# SWD.net
KiCad netlist of a schematic drawn in EAGLE
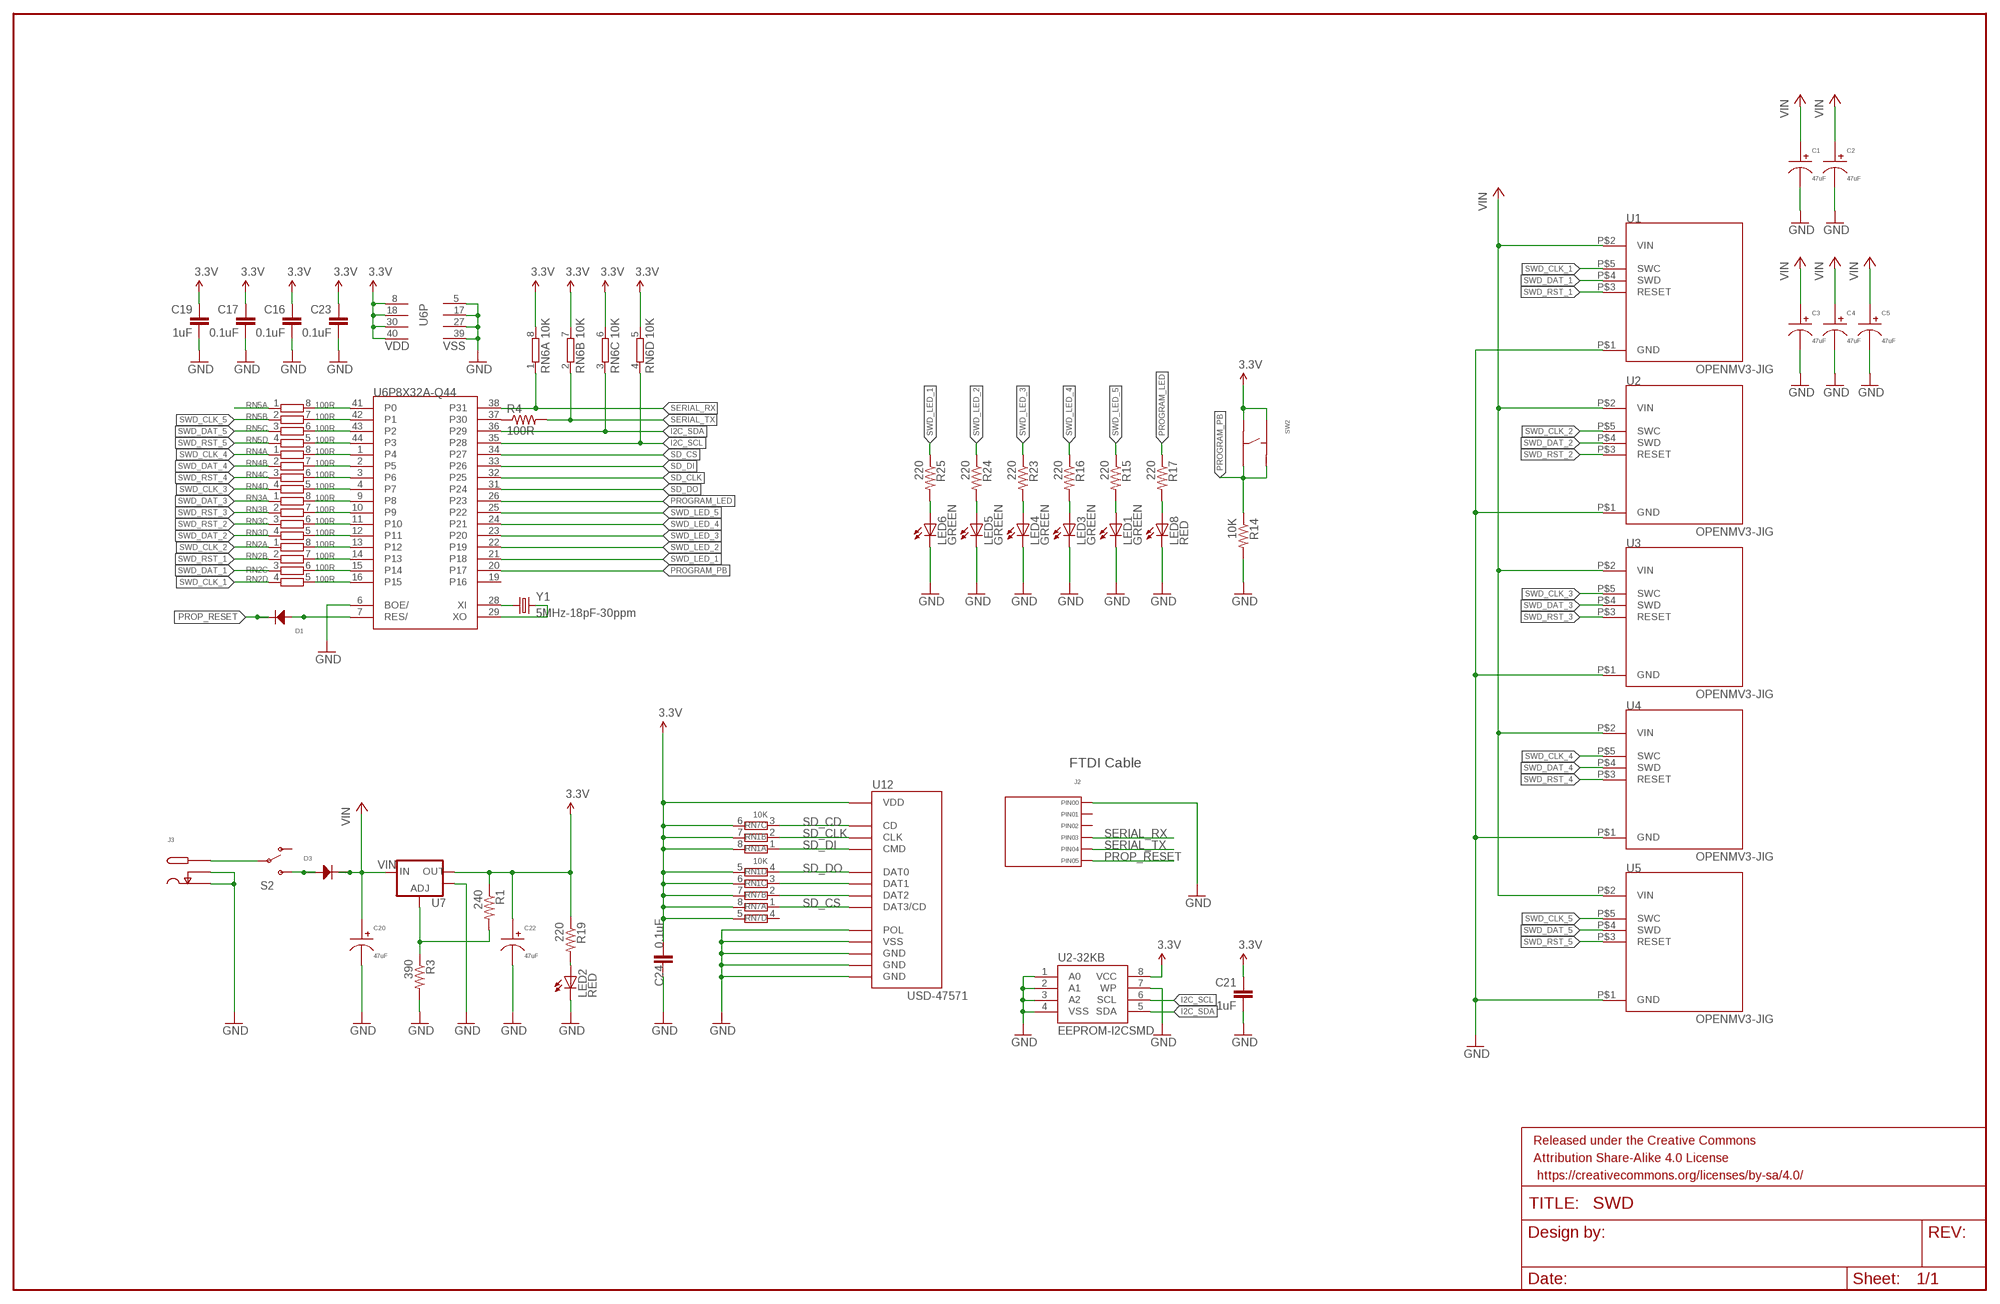
[diagram p0: schematic, sheet 1]

(export (version "E")
  (design (tool "Eeschema 10.0.6"))
  (components
    (comp (ref "C1")
      (value "47uF")
      (footprint "eagle-import:CP6.3MM")
      (fields (field (name "MFG#") "N/A") (field (name "TOLERANCE") "N/A") (field (name "VOTLAGE") "N/A"))
      (libsource (lib "eagle-import") (part "CAPACITOR_P_6.3MM"))
    )
    (comp (ref "C2")
      (value "47uF")
      (footprint "eagle-import:CP6.3MM")
      (fields (field (name "MFG#") "N/A") (field (name "TOLERANCE") "N/A") (field (name "VOTLAGE") "N/A"))
      (libsource (lib "eagle-import") (part "CAPACITOR_P_6.3MM"))
    )
    (comp (ref "C3")
      (value "47uF")
      (footprint "eagle-import:CP6.3MM")
      (fields (field (name "MFG#") "N/A") (field (name "TOLERANCE") "N/A") (field (name "VOTLAGE") "N/A"))
      (libsource (lib "eagle-import") (part "CAPACITOR_P_6.3MM"))
    )
    (comp (ref "C4")
      (value "47uF")
      (footprint "eagle-import:CP6.3MM")
      (fields (field (name "MFG#") "N/A") (field (name "TOLERANCE") "N/A") (field (name "VOTLAGE") "N/A"))
      (libsource (lib "eagle-import") (part "CAPACITOR_P_6.3MM"))
    )
    (comp (ref "C5")
      (value "47uF")
      (footprint "eagle-import:CP6.3MM")
      (fields (field (name "MFG#") "N/A") (field (name "TOLERANCE") "N/A") (field (name "VOTLAGE") "N/A"))
      (libsource (lib "eagle-import") (part "CAPACITOR_P_6.3MM"))
    )
    (comp (ref "C16")
      (value "0.1uF")
      (footprint "eagle-import:0603-CAP")
      (libsource (lib "eagle-import") (part "CAP0603-CAP"))
    )
    (comp (ref "C17")
      (value "0.1uF")
      (footprint "eagle-import:0603-CAP")
      (libsource (lib "eagle-import") (part "CAP0603-CAP"))
    )
    (comp (ref "C19")
      (value "1uF")
      (footprint "eagle-import:0603-CAP")
      (libsource (lib "eagle-import") (part "CAP0603-CAP"))
    )
    (comp (ref "C20")
      (value "47uF")
      (footprint "eagle-import:CP6.3MM")
      (libsource (lib "eagle-import") (part "CAPACITOR_P_6.3MM"))
    )
    (comp (ref "C21")
      (value "1uF")
      (footprint "eagle-import:0603-CAP")
      (libsource (lib "eagle-import") (part "CAP0603-CAP"))
    )
    (comp (ref "C22")
      (value "47uF")
      (footprint "eagle-import:CP6.3MM")
      (libsource (lib "eagle-import") (part "CAPACITOR_P_6.3MM"))
    )
    (comp (ref "C23")
      (value "0.1uF")
      (footprint "eagle-import:0603-CAP")
      (libsource (lib "eagle-import") (part "CAP0603-CAP"))
    )
    (comp (ref "C24")
      (value "0.1uF")
      (footprint "eagle-import:0603-CAP")
      (libsource (lib "eagle-import") (part "CAP0603-CAP"))
    )
    (comp (ref "D1")
      (value "DIODE_SOD-123")
      (footprint "eagle-import:SOD-123")
      (libsource (lib "eagle-import") (part "DIODE_SOD-123"))
    )
    (comp (ref "D3")
      (value "DIODE_SMA")
      (footprint "eagle-import:SMA")
      (libsource (lib "eagle-import") (part "DIODE_SMA"))
    )
    (comp (ref "FRAME1")
      (value "FRAME-LEDGER")
      (footprint "eagle-import:CREATIVE_COMMONS")
      (libsource (lib "eagle-import") (part "FRAME-LEDGER"))
    )
    (comp (ref "J2")
      (value "HEADER_01X06_PTH_2.54MM")
      (footprint "eagle-import:PTH_2.54MM_01X06")
      (libsource (lib "eagle-import") (part "HEADER_01X06_PTH_2.54MM"))
    )
    (comp (ref "J3")
      (value "DC_PWR_JACK_2.5MM_RIGHT")
      (footprint "eagle-import:DC_PWR_JACK")
      (libsource (lib "eagle-import") (part "DC_PWR_JACK_2.5MM_RIGHT"))
    )
    (comp (ref "LED1")
      (value "GREEN")
      (footprint "eagle-import:LED-0603")
      (libsource (lib "eagle-import") (part "LED0603"))
    )
    (comp (ref "LED2")
      (value "RED")
      (footprint "eagle-import:LED-0603")
      (libsource (lib "eagle-import") (part "LED0603"))
    )
    (comp (ref "LED3")
      (value "GREEN")
      (footprint "eagle-import:LED-0603")
      (libsource (lib "eagle-import") (part "LED0603"))
    )
    (comp (ref "LED4")
      (value "GREEN")
      (footprint "eagle-import:LED-0603")
      (libsource (lib "eagle-import") (part "LED0603"))
    )
    (comp (ref "LED5")
      (value "GREEN")
      (footprint "eagle-import:LED-0603")
      (libsource (lib "eagle-import") (part "LED0603"))
    )
    (comp (ref "LED6")
      (value "GREEN")
      (footprint "eagle-import:LED-0603")
      (libsource (lib "eagle-import") (part "LED0603"))
    )
    (comp (ref "LED8")
      (value "RED")
      (footprint "eagle-import:LED-0603")
      (libsource (lib "eagle-import") (part "LED0603"))
    )
    (comp (ref "R1")
      (value "240")
      (footprint "eagle-import:0603-RES")
      (libsource (lib "eagle-import") (part "RESISTOR0603-RES"))
    )
    (comp (ref "R3")
      (value "390")
      (footprint "eagle-import:0603-RES")
      (libsource (lib "eagle-import") (part "RESISTOR0603-RES"))
    )
    (comp (ref "R4")
      (value "100R")
      (footprint "eagle-import:0603-RES")
      (libsource (lib "eagle-import") (part "RESISTOR0603-RES"))
    )
    (comp (ref "R14")
      (value "10K")
      (footprint "eagle-import:0603-RES")
      (libsource (lib "eagle-import") (part "RESISTOR0603-RES"))
    )
    (comp (ref "R15")
      (value "220")
      (footprint "eagle-import:0603-RES")
      (libsource (lib "eagle-import") (part "RESISTOR0603-RES"))
    )
    (comp (ref "R16")
      (value "220")
      (footprint "eagle-import:0603-RES")
      (libsource (lib "eagle-import") (part "RESISTOR0603-RES"))
    )
    (comp (ref "R17")
      (value "220")
      (footprint "eagle-import:0603-RES")
      (libsource (lib "eagle-import") (part "RESISTOR0603-RES"))
    )
    (comp (ref "R19")
      (value "220")
      (footprint "eagle-import:0603-RES")
      (libsource (lib "eagle-import") (part "RESISTOR0603-RES"))
    )
    (comp (ref "R23")
      (value "220")
      (footprint "eagle-import:0603-RES")
      (libsource (lib "eagle-import") (part "RESISTOR0603-RES"))
    )
    (comp (ref "R24")
      (value "220")
      (footprint "eagle-import:0603-RES")
      (libsource (lib "eagle-import") (part "RESISTOR0603-RES"))
    )
    (comp (ref "R25")
      (value "220")
      (footprint "eagle-import:0603-RES")
      (libsource (lib "eagle-import") (part "RESISTOR0603-RES"))
    )
    (comp (ref "RN1")
      (value "10K")
      (footprint "eagle-import:EXBV8V")
      (fields (field (name "OC_FARNELL") "unknown") (field (name "OC_NEWARK") "unknown"))
      (libsource (lib "eagle-import") (part "4R-NEXBV8V"))
    )
    (comp (ref "RN2")
      (value "100R")
      (footprint "eagle-import:EXBV8V")
      (fields (field (name "OC_FARNELL") "unknown") (field (name "OC_NEWARK") "unknown"))
      (libsource (lib "eagle-import") (part "4R-NEXBV8V"))
    )
    (comp (ref "RN3")
      (value "100R")
      (footprint "eagle-import:EXBV8V")
      (fields (field (name "OC_FARNELL") "unknown") (field (name "OC_NEWARK") "unknown"))
      (libsource (lib "eagle-import") (part "4R-NEXBV8V"))
    )
    (comp (ref "RN4")
      (value "100R")
      (footprint "eagle-import:EXBV8V")
      (fields (field (name "OC_FARNELL") "unknown") (field (name "OC_NEWARK") "unknown"))
      (libsource (lib "eagle-import") (part "4R-NEXBV8V"))
    )
    (comp (ref "RN5")
      (value "100R")
      (footprint "eagle-import:EXBV8V")
      (fields (field (name "OC_FARNELL") "unknown") (field (name "OC_NEWARK") "unknown"))
      (libsource (lib "eagle-import") (part "4R-NEXBV8V"))
    )
    (comp (ref "RN6")
      (value "10K")
      (footprint "eagle-import:EXBV8V")
      (fields (field (name "OC_FARNELL") "unknown") (field (name "OC_NEWARK") "unknown"))
      (libsource (lib "eagle-import") (part "4R-NEXBV8V"))
    )
    (comp (ref "RN7")
      (value "10K")
      (footprint "eagle-import:EXBV8V")
      (fields (field (name "OC_FARNELL") "unknown") (field (name "OC_NEWARK") "unknown"))
      (libsource (lib "eagle-import") (part "4R-NEXBV8V"))
    )
    (comp (ref "S2")
      (value "SWITCH-SPSTPTH")
      (footprint "eagle-import:SWITCH-SPDT")
      (libsource (lib "eagle-import") (part "SWITCH-SPSTPTH"))
    )
    (comp (ref "SW2")
      (value "TACT_6MM")
      (footprint "eagle-import:TACT6MM")
      (libsource (lib "eagle-import") (part "TACT_6MM"))
    )
    (comp (ref "U1")
      (value "OPENMV3-JIG")
      (footprint "eagle-import:OPENMV3-JIG")
      (libsource (lib "eagle-import") (part "OPENMV3-JIG"))
    )
    (comp (ref "U2")
      (value "OPENMV3-JIG")
      (footprint "eagle-import:OPENMV3-JIG")
      (libsource (lib "eagle-import") (part "OPENMV3-JIG"))
    )
    (comp (ref "U2-32KB")
      (value "EEPROM-I2CSMD")
      (footprint "eagle-import:SO08")
      (libsource (lib "eagle-import") (part "EEPROM-I2CSMD"))
    )
    (comp (ref "U3")
      (value "OPENMV3-JIG")
      (footprint "eagle-import:OPENMV3-JIG")
      (libsource (lib "eagle-import") (part "OPENMV3-JIG"))
    )
    (comp (ref "U4")
      (value "OPENMV3-JIG")
      (footprint "eagle-import:OPENMV3-JIG")
      (libsource (lib "eagle-import") (part "OPENMV3-JIG"))
    )
    (comp (ref "U5")
      (value "OPENMV3-JIG")
      (footprint "eagle-import:OPENMV3-JIG")
      (libsource (lib "eagle-import") (part "OPENMV3-JIG"))
    )
    (comp (ref "U6")
      (value "P8X32A-Q44")
      (footprint "eagle-import:P8X32A-Q44")
      (libsource (lib "eagle-import") (part "P8X32A-Q44"))
    )
    (comp (ref "U7")
      (value "V_REG_LM1117SOT223")
      (footprint "eagle-import:SOT223")
      (libsource (lib "eagle-import") (part "V_REG_LM1117SOT223"))
    )
    (comp (ref "U12")
      (value "USD-47571")
      (footprint "eagle-import:USD-47571")
      (libsource (lib "eagle-import") (part "USD-47571"))
    )
    (comp (ref "Y1")
      (value "5MHz-18pF-30ppm")
      (footprint "eagle-import:HC49UP")
      (libsource (lib "eagle-import") (part "CRYSTALSMD"))
    )
  )
  (nets
    (net (code "1") (name "/SD_CD") (class "Default")
      (node (ref "RN7") (pin "3") (pinfunction "1_3") (pintype "passive"))
      (node (ref "U12") (pin "G$5") (pinfunction "CD_G$5") (pintype "power_in"))
    )
    (net (code "2") (name "3.3V") (class "Default")
      (node (ref "C16") (pin "1") (pinfunction "1_1") (pintype "passive"))
      (node (ref "C17") (pin "1") (pinfunction "1_1") (pintype "passive"))
      (node (ref "C19") (pin "1") (pinfunction "1_1") (pintype "passive"))
      (node (ref "C21") (pin "1") (pinfunction "1_1") (pintype "passive"))
      (node (ref "C22") (pin "P$1") (pinfunction "P$1_P$1") (pintype "passive"))
      (node (ref "C23") (pin "1") (pinfunction "1_1") (pintype "passive"))
      (node (ref "C24") (pin "1") (pinfunction "1_1") (pintype "passive"))
      (node (ref "R1") (pin "1") (pinfunction "1_1") (pintype "passive"))
      (node (ref "R19") (pin "1") (pinfunction "1_1") (pintype "passive"))
      (node (ref "RN1") (pin "5") (pinfunction "2_5") (pintype "passive"))
      (node (ref "RN1") (pin "6") (pinfunction "2_6") (pintype "passive"))
      (node (ref "RN1") (pin "7") (pinfunction "2_7") (pintype "passive"))
      (node (ref "RN1") (pin "8") (pinfunction "2_8") (pintype "passive"))
      (node (ref "RN6") (pin "5") (pinfunction "2_5") (pintype "passive"))
      (node (ref "RN6") (pin "6") (pinfunction "2_6") (pintype "passive"))
      (node (ref "RN6") (pin "7") (pinfunction "2_7") (pintype "passive"))
      (node (ref "RN6") (pin "8") (pinfunction "2_8") (pintype "passive"))
      (node (ref "RN7") (pin "5") (pinfunction "2_5") (pintype "passive"))
      (node (ref "RN7") (pin "6") (pinfunction "2_6") (pintype "passive"))
      (node (ref "RN7") (pin "7") (pinfunction "2_7") (pintype "passive"))
      (node (ref "RN7") (pin "8") (pinfunction "2_8") (pintype "passive"))
      (node (ref "SW2") (pin "P$1") (pinfunction "P$1_P$1") (pintype "bidirectional"))
      (node (ref "SW2") (pin "P$3") (pinfunction "P$3_P$3") (pintype "bidirectional"))
      (node (ref "U12") (pin "P$4") (pinfunction "VDD_P$4") (pintype "power_in"))
      (node (ref "U2-32KB") (pin "8") (pinfunction "VCC_8") (pintype "power_in"))
      (node (ref "U6") (pin "18") (pinfunction "VDD_18") (pintype "power_in"))
      (node (ref "U6") (pin "30") (pinfunction "VDD_30") (pintype "power_in"))
      (node (ref "U6") (pin "40") (pinfunction "VDD_40") (pintype "power_in"))
      (node (ref "U6") (pin "8") (pinfunction "VDD_8") (pintype "power_in"))
      (node (ref "U7") (pin "2") (pinfunction "OUT_2") (pintype "output"))
    )
    (net (code "3") (name "GND") (class "Default")
      (node (ref "C1") (pin "P$2") (pinfunction "P$2_P$2") (pintype "passive"))
      (node (ref "C16") (pin "2") (pinfunction "2_2") (pintype "passive"))
      (node (ref "C17") (pin "2") (pinfunction "2_2") (pintype "passive"))
      (node (ref "C19") (pin "2") (pinfunction "2_2") (pintype "passive"))
      (node (ref "C2") (pin "P$2") (pinfunction "P$2_P$2") (pintype "passive"))
      (node (ref "C20") (pin "P$2") (pinfunction "P$2_P$2") (pintype "passive"))
      (node (ref "C21") (pin "2") (pinfunction "2_2") (pintype "passive"))
      (node (ref "C22") (pin "P$2") (pinfunction "P$2_P$2") (pintype "passive"))
      (node (ref "C23") (pin "2") (pinfunction "2_2") (pintype "passive"))
      (node (ref "C24") (pin "2") (pinfunction "2_2") (pintype "passive"))
      (node (ref "C3") (pin "P$2") (pinfunction "P$2_P$2") (pintype "passive"))
      (node (ref "C4") (pin "P$2") (pinfunction "P$2_P$2") (pintype "passive"))
      (node (ref "C5") (pin "P$2") (pinfunction "P$2_P$2") (pintype "passive"))
      (node (ref "J2") (pin "P$1") (pinfunction "PIN0_P$1") (pintype "bidirectional"))
      (node (ref "J3") (pin "SLEEVE1") (pinfunction "SLEEVE_SLEEVE1") (pintype "power_in"))
      (node (ref "J3") (pin "SLEEVE2") (pinfunction "SLEEVE_SHUNT_SLEEVE2") (pintype "power_in"))
      (node (ref "LED1") (pin "C") (pinfunction "C_C") (pintype "passive"))
      (node (ref "LED2") (pin "C") (pinfunction "C_C") (pintype "passive"))
      (node (ref "LED3") (pin "C") (pinfunction "C_C") (pintype "passive"))
      (node (ref "LED4") (pin "C") (pinfunction "C_C") (pintype "passive"))
      (node (ref "LED5") (pin "C") (pinfunction "C_C") (pintype "passive"))
      (node (ref "LED6") (pin "C") (pinfunction "C_C") (pintype "passive"))
      (node (ref "LED8") (pin "C") (pinfunction "C_C") (pintype "passive"))
      (node (ref "R14") (pin "2") (pinfunction "2_2") (pintype "passive"))
      (node (ref "R3") (pin "2") (pinfunction "2_2") (pintype "passive"))
      (node (ref "U1") (pin "P$1") (pinfunction "GND_P$1") (pintype "power_in"))
      (node (ref "U12") (pin "G$1") (pinfunction "GND_G$1") (pintype "power_in"))
      (node (ref "U12") (pin "G$2") (pinfunction "GND_G$2") (pintype "power_in"))
      (node (ref "U12") (pin "G$3") (pinfunction "GND_G$3") (pintype "power_in"))
      (node (ref "U12") (pin "G$4") (pinfunction "POL_G$4") (pintype "power_in"))
      (node (ref "U12") (pin "P$6") (pinfunction "VSS_P$6") (pintype "power_in"))
      (node (ref "U2") (pin "P$1") (pinfunction "GND_P$1") (pintype "power_in"))
      (node (ref "U2-32KB") (pin "1") (pinfunction "A0_1") (pintype "bidirectional"))
      (node (ref "U2-32KB") (pin "2") (pinfunction "A1_2") (pintype "bidirectional"))
      (node (ref "U2-32KB") (pin "3") (pinfunction "A2_3") (pintype "bidirectional"))
      (node (ref "U2-32KB") (pin "4") (pinfunction "VSS_4") (pintype "power_in"))
      (node (ref "U2-32KB") (pin "7") (pinfunction "WP_7") (pintype "bidirectional"))
      (node (ref "U3") (pin "P$1") (pinfunction "GND_P$1") (pintype "power_in"))
      (node (ref "U4") (pin "P$1") (pinfunction "GND_P$1") (pintype "power_in"))
      (node (ref "U5") (pin "P$1") (pinfunction "GND_P$1") (pintype "power_in"))
      (node (ref "U6") (pin "17") (pinfunction "VSS_17") (pintype "power_in"))
      (node (ref "U6") (pin "27") (pinfunction "VSS_27") (pintype "power_in"))
      (node (ref "U6") (pin "39") (pinfunction "VSS_39") (pintype "power_in"))
      (node (ref "U6") (pin "5") (pinfunction "VSS_5") (pintype "power_in"))
      (node (ref "U6") (pin "6") (pinfunction "BOE/_6") (pintype "input"))
      (node (ref "U7") (pin "4") (pinfunction "OUT_4") (pintype "output"))
    )
    (net (code "4") (name "I2C_SCL") (class "Default")
      (node (ref "RN6") (pin "4") (pinfunction "1_4") (pintype "passive"))
      (node (ref "U2-32KB") (pin "6") (pinfunction "SCL_6") (pintype "bidirectional"))
      (node (ref "U6") (pin "35") (pinfunction "P28_35") (pintype "bidirectional"))
    )
    (net (code "5") (name "I2C_SDA") (class "Default")
      (node (ref "RN6") (pin "3") (pinfunction "1_3") (pintype "passive"))
      (node (ref "U2-32KB") (pin "5") (pinfunction "SDA_5") (pintype "bidirectional"))
      (node (ref "U6") (pin "36") (pinfunction "P29_36") (pintype "bidirectional"))
    )
    (net (code "6") (name "Net-(LED1-PadA)") (class "Default")
      (node (ref "LED1") (pin "A") (pinfunction "A_A") (pintype "passive"))
      (node (ref "R15") (pin "2") (pinfunction "2_2") (pintype "passive"))
    )
    (net (code "7") (name "Net-(LED2-PadA)") (class "Default")
      (node (ref "LED2") (pin "A") (pinfunction "A_A") (pintype "passive"))
      (node (ref "R19") (pin "2") (pinfunction "2_2") (pintype "passive"))
    )
    (net (code "8") (name "Net-(LED3-PadA)") (class "Default")
      (node (ref "LED3") (pin "A") (pinfunction "A_A") (pintype "passive"))
      (node (ref "R16") (pin "2") (pinfunction "2_2") (pintype "passive"))
    )
    (net (code "9") (name "Net-(LED4-PadA)") (class "Default")
      (node (ref "LED4") (pin "A") (pinfunction "A_A") (pintype "passive"))
      (node (ref "R23") (pin "2") (pinfunction "2_2") (pintype "passive"))
    )
    (net (code "10") (name "Net-(LED5-PadA)") (class "Default")
      (node (ref "LED5") (pin "A") (pinfunction "A_A") (pintype "passive"))
      (node (ref "R24") (pin "2") (pinfunction "2_2") (pintype "passive"))
    )
    (net (code "11") (name "Net-(LED6-PadA)") (class "Default")
      (node (ref "LED6") (pin "A") (pinfunction "A_A") (pintype "passive"))
      (node (ref "R25") (pin "2") (pinfunction "2_2") (pintype "passive"))
    )
    (net (code "12") (name "Net-(LED8-PadA)") (class "Default")
      (node (ref "LED8") (pin "A") (pinfunction "A_A") (pintype "passive"))
      (node (ref "R17") (pin "2") (pinfunction "2_2") (pintype "passive"))
    )
    (net (code "13") (name "Net-(RN1C-1)") (class "Default")
      (node (ref "RN1") (pin "3") (pinfunction "1_3") (pintype "passive"))
      (node (ref "U12") (pin "P$8") (pinfunction "DAT1_P$8") (pintype "bidirectional"))
    )
    (net (code "14") (name "Net-(RN2A-2)") (class "Default")
      (node (ref "RN2") (pin "8") (pinfunction "2_8") (pintype "passive"))
      (node (ref "U6") (pin "13") (pinfunction "P12_13") (pintype "bidirectional"))
    )
    (net (code "15") (name "Net-(RN2B-2)") (class "Default")
      (node (ref "RN2") (pin "7") (pinfunction "2_7") (pintype "passive"))
      (node (ref "U6") (pin "14") (pinfunction "P13_14") (pintype "bidirectional"))
    )
    (net (code "16") (name "Net-(RN2C-2)") (class "Default")
      (node (ref "RN2") (pin "6") (pinfunction "2_6") (pintype "passive"))
      (node (ref "U6") (pin "15") (pinfunction "P14_15") (pintype "bidirectional"))
    )
    (net (code "17") (name "Net-(RN2D-2)") (class "Default")
      (node (ref "RN2") (pin "5") (pinfunction "2_5") (pintype "passive"))
      (node (ref "U6") (pin "16") (pinfunction "P15_16") (pintype "bidirectional"))
    )
    (net (code "18") (name "Net-(RN3A-2)") (class "Default")
      (node (ref "RN3") (pin "8") (pinfunction "2_8") (pintype "passive"))
      (node (ref "U6") (pin "9") (pinfunction "P8_9") (pintype "bidirectional"))
    )
    (net (code "19") (name "Net-(RN3B-2)") (class "Default")
      (node (ref "RN3") (pin "7") (pinfunction "2_7") (pintype "passive"))
      (node (ref "U6") (pin "10") (pinfunction "P9_10") (pintype "bidirectional"))
    )
    (net (code "20") (name "Net-(RN3C-2)") (class "Default")
      (node (ref "RN3") (pin "6") (pinfunction "2_6") (pintype "passive"))
      (node (ref "U6") (pin "11") (pinfunction "P10_11") (pintype "bidirectional"))
    )
    (net (code "21") (name "Net-(RN3D-2)") (class "Default")
      (node (ref "RN3") (pin "5") (pinfunction "2_5") (pintype "passive"))
      (node (ref "U6") (pin "12") (pinfunction "P11_12") (pintype "bidirectional"))
    )
    (net (code "22") (name "Net-(RN4A-2)") (class "Default")
      (node (ref "RN4") (pin "8") (pinfunction "2_8") (pintype "passive"))
      (node (ref "U6") (pin "1") (pinfunction "P4_1") (pintype "bidirectional"))
    )
    (net (code "23") (name "Net-(RN4B-2)") (class "Default")
      (node (ref "RN4") (pin "7") (pinfunction "2_7") (pintype "passive"))
      (node (ref "U6") (pin "2") (pinfunction "P5_2") (pintype "bidirectional"))
    )
    (net (code "24") (name "Net-(RN4C-2)") (class "Default")
      (node (ref "RN4") (pin "6") (pinfunction "2_6") (pintype "passive"))
      (node (ref "U6") (pin "3") (pinfunction "P6_3") (pintype "bidirectional"))
    )
    (net (code "25") (name "Net-(RN4D-2)") (class "Default")
      (node (ref "RN4") (pin "5") (pinfunction "2_5") (pintype "passive"))
      (node (ref "U6") (pin "4") (pinfunction "P7_4") (pintype "bidirectional"))
    )
    (net (code "26") (name "Net-(RN5A-2)") (class "Default")
      (node (ref "RN5") (pin "8") (pinfunction "2_8") (pintype "passive"))
      (node (ref "U6") (pin "41") (pinfunction "P0_41") (pintype "bidirectional"))
    )
    (net (code "27") (name "Net-(RN5B-2)") (class "Default")
      (node (ref "RN5") (pin "7") (pinfunction "2_7") (pintype "passive"))
      (node (ref "U6") (pin "42") (pinfunction "P1_42") (pintype "bidirectional"))
    )
    (net (code "28") (name "Net-(RN5C-2)") (class "Default")
      (node (ref "RN5") (pin "6") (pinfunction "2_6") (pintype "passive"))
      (node (ref "U6") (pin "43") (pinfunction "P2_43") (pintype "bidirectional"))
    )
    (net (code "29") (name "Net-(RN5D-2)") (class "Default")
      (node (ref "RN5") (pin "5") (pinfunction "2_5") (pintype "passive"))
      (node (ref "U6") (pin "44") (pinfunction "P3_44") (pintype "bidirectional"))
    )
    (net (code "30") (name "Net-(RN7B-1)") (class "Default")
      (node (ref "RN7") (pin "2") (pinfunction "1_2") (pintype "passive"))
      (node (ref "U12") (pin "P$1") (pinfunction "DAT2_P$1") (pintype "bidirectional"))
    )
    (net (code "31") (name "Net-(S2-P)") (class "Default")
      (node (ref "J3") (pin "PIN") (pinfunction "PIN_PIN") (pintype "power_in"))
      (node (ref "S2") (pin "2") (pinfunction "P_2") (pintype "passive"))
    )
    (net (code "32") (name "Net-(S2-S)") (class "Default")
      (node (ref "D3") (pin "ANODE") (pinfunction "ANODE_ANODE") (pintype "bidirectional"))
      (node (ref "S2") (pin "3") (pinfunction "S_3") (pintype "passive"))
    )
    (net (code "33") (name "Net-(U6B-P30)") (class "Default")
      (node (ref "R4") (pin "1") (pinfunction "1_1") (pintype "passive"))
      (node (ref "U6") (pin "37") (pinfunction "P30_37") (pintype "bidirectional"))
    )
    (net (code "34") (name "Net-(U6B-RES{slash})") (class "Default")
      (node (ref "D1") (pin "ANODE") (pinfunction "ANODE_ANODE") (pintype "bidirectional"))
      (node (ref "U6") (pin "7") (pinfunction "RES/_7") (pintype "bidirectional"))
    )
    (net (code "35") (name "Net-(U6B-XI)") (class "Default")
      (node (ref "U6") (pin "28") (pinfunction "XI_28") (pintype "input"))
      (node (ref "Y1") (pin "1") (pinfunction "1_1") (pintype "passive"))
    )
    (net (code "36") (name "Net-(U6B-XO)") (class "Default")
      (node (ref "U6") (pin "29") (pinfunction "XO_29") (pintype "output"))
      (node (ref "Y1") (pin "2") (pinfunction "2_2") (pintype "passive"))
    )
    (net (code "37") (name "Net-(U7-ADJ)") (class "Default")
      (node (ref "R1") (pin "2") (pinfunction "2_2") (pintype "passive"))
      (node (ref "R3") (pin "1") (pinfunction "1_1") (pintype "passive"))
      (node (ref "U7") (pin "1") (pinfunction "ADJ_1") (pintype "input"))
    )
    (net (code "38") (name "PROGRAM_LED") (class "Default")
      (node (ref "R17") (pin "1") (pinfunction "1_1") (pintype "passive"))
      (node (ref "U6") (pin "26") (pinfunction "P23_26") (pintype "bidirectional"))
    )
    (net (code "39") (name "PROGRAM_PB") (class "Default")
      (node (ref "R14") (pin "1") (pinfunction "1_1") (pintype "passive"))
      (node (ref "SW2") (pin "P$2") (pinfunction "P$2_P$2") (pintype "bidirectional"))
      (node (ref "SW2") (pin "P$4") (pinfunction "P$4_P$4") (pintype "bidirectional"))
      (node (ref "U6") (pin "20") (pinfunction "P17_20") (pintype "bidirectional"))
    )
    (net (code "40") (name "PROP_RESET") (class "Default")
      (node (ref "D1") (pin "CATHODE") (pinfunction "CATHODE_CATHODE") (pintype "bidirectional"))
      (node (ref "J2") (pin "P$6") (pinfunction "PIN5_P$6") (pintype "bidirectional"))
    )
    (net (code "41") (name "SD_CLK") (class "Default")
      (node (ref "RN1") (pin "2") (pinfunction "1_2") (pintype "passive"))
      (node (ref "U12") (pin "P$5") (pinfunction "CLK_P$5") (pintype "bidirectional"))
      (node (ref "U6") (pin "32") (pinfunction "P25_32") (pintype "bidirectional"))
    )
    (net (code "42") (name "SD_CS") (class "Default")
      (node (ref "RN7") (pin "1") (pinfunction "1_1") (pintype "passive"))
      (node (ref "U12") (pin "P$2") (pinfunction "DAT3/CD_P$2") (pintype "bidirectional"))
      (node (ref "U6") (pin "34") (pinfunction "P27_34") (pintype "bidirectional"))
    )
    (net (code "43") (name "SD_DI") (class "Default")
      (node (ref "RN1") (pin "1") (pinfunction "1_1") (pintype "passive"))
      (node (ref "U12") (pin "P$3") (pinfunction "CMD_P$3") (pintype "bidirectional"))
      (node (ref "U6") (pin "33") (pinfunction "P26_33") (pintype "bidirectional"))
    )
    (net (code "44") (name "SD_DO") (class "Default")
      (node (ref "RN1") (pin "4") (pinfunction "1_4") (pintype "passive"))
      (node (ref "U12") (pin "P$7") (pinfunction "DAT0_P$7") (pintype "bidirectional"))
      (node (ref "U6") (pin "31") (pinfunction "P24_31") (pintype "bidirectional"))
    )
    (net (code "45") (name "SERIAL_RX") (class "Default")
      (node (ref "J2") (pin "P$4") (pinfunction "PIN3_P$4") (pintype "bidirectional"))
      (node (ref "RN6") (pin "1") (pinfunction "1_1") (pintype "passive"))
      (node (ref "U6") (pin "38") (pinfunction "P31_38") (pintype "bidirectional"))
    )
    (net (code "46") (name "SERIAL_TX") (class "Default")
      (node (ref "J2") (pin "P$5") (pinfunction "PIN4_P$5") (pintype "bidirectional"))
      (node (ref "R4") (pin "2") (pinfunction "2_2") (pintype "passive"))
      (node (ref "RN6") (pin "2") (pinfunction "1_2") (pintype "passive"))
    )
    (net (code "47") (name "SWD_CLK_1") (class "Default")
      (node (ref "RN2") (pin "4") (pinfunction "1_4") (pintype "passive"))
      (node (ref "U1") (pin "P$5") (pinfunction "SWC_P$5") (pintype "bidirectional"))
    )
    (net (code "48") (name "SWD_CLK_2") (class "Default")
      (node (ref "RN2") (pin "1") (pinfunction "1_1") (pintype "passive"))
      (node (ref "U2") (pin "P$5") (pinfunction "SWC_P$5") (pintype "bidirectional"))
    )
    (net (code "49") (name "SWD_CLK_3") (class "Default")
      (node (ref "RN4") (pin "4") (pinfunction "1_4") (pintype "passive"))
      (node (ref "U3") (pin "P$5") (pinfunction "SWC_P$5") (pintype "bidirectional"))
    )
    (net (code "50") (name "SWD_CLK_4") (class "Default")
      (node (ref "RN4") (pin "1") (pinfunction "1_1") (pintype "passive"))
      (node (ref "U4") (pin "P$5") (pinfunction "SWC_P$5") (pintype "bidirectional"))
    )
    (net (code "51") (name "SWD_CLK_5") (class "Default")
      (node (ref "RN5") (pin "2") (pinfunction "1_2") (pintype "passive"))
      (node (ref "U5") (pin "P$5") (pinfunction "SWC_P$5") (pintype "bidirectional"))
    )
    (net (code "52") (name "SWD_DAT_1") (class "Default")
      (node (ref "RN2") (pin "3") (pinfunction "1_3") (pintype "passive"))
      (node (ref "U1") (pin "P$4") (pinfunction "SWD_P$4") (pintype "bidirectional"))
    )
    (net (code "53") (name "SWD_DAT_2") (class "Default")
      (node (ref "RN3") (pin "4") (pinfunction "1_4") (pintype "passive"))
      (node (ref "U2") (pin "P$4") (pinfunction "SWD_P$4") (pintype "bidirectional"))
    )
    (net (code "54") (name "SWD_DAT_3") (class "Default")
      (node (ref "RN3") (pin "1") (pinfunction "1_1") (pintype "passive"))
      (node (ref "U3") (pin "P$4") (pinfunction "SWD_P$4") (pintype "bidirectional"))
    )
    (net (code "55") (name "SWD_DAT_4") (class "Default")
      (node (ref "RN4") (pin "2") (pinfunction "1_2") (pintype "passive"))
      (node (ref "U4") (pin "P$4") (pinfunction "SWD_P$4") (pintype "bidirectional"))
    )
    (net (code "56") (name "SWD_DAT_5") (class "Default")
      (node (ref "RN5") (pin "3") (pinfunction "1_3") (pintype "passive"))
      (node (ref "U5") (pin "P$4") (pinfunction "SWD_P$4") (pintype "bidirectional"))
    )
    (net (code "57") (name "SWD_LED_1") (class "Default")
      (node (ref "R25") (pin "1") (pinfunction "1_1") (pintype "passive"))
      (node (ref "U6") (pin "21") (pinfunction "P18_21") (pintype "bidirectional"))
    )
    (net (code "58") (name "SWD_LED_2") (class "Default")
      (node (ref "R24") (pin "1") (pinfunction "1_1") (pintype "passive"))
      (node (ref "U6") (pin "22") (pinfunction "P19_22") (pintype "bidirectional"))
    )
    (net (code "59") (name "SWD_LED_3") (class "Default")
      (node (ref "R23") (pin "1") (pinfunction "1_1") (pintype "passive"))
      (node (ref "U6") (pin "23") (pinfunction "P20_23") (pintype "bidirectional"))
    )
    (net (code "60") (name "SWD_LED_4") (class "Default")
      (node (ref "R16") (pin "1") (pinfunction "1_1") (pintype "passive"))
      (node (ref "U6") (pin "24") (pinfunction "P21_24") (pintype "bidirectional"))
    )
    (net (code "61") (name "SWD_LED_5") (class "Default")
      (node (ref "R15") (pin "1") (pinfunction "1_1") (pintype "passive"))
      (node (ref "U6") (pin "25") (pinfunction "P22_25") (pintype "bidirectional"))
    )
    (net (code "62") (name "SWD_RST_1") (class "Default")
      (node (ref "RN2") (pin "2") (pinfunction "1_2") (pintype "passive"))
      (node (ref "U1") (pin "P$3") (pinfunction "RESET_P$3") (pintype "bidirectional"))
    )
    (net (code "63") (name "SWD_RST_2") (class "Default")
      (node (ref "RN3") (pin "3") (pinfunction "1_3") (pintype "passive"))
      (node (ref "U2") (pin "P$3") (pinfunction "RESET_P$3") (pintype "bidirectional"))
    )
    (net (code "64") (name "SWD_RST_3") (class "Default")
      (node (ref "RN3") (pin "2") (pinfunction "1_2") (pintype "passive"))
      (node (ref "U3") (pin "P$3") (pinfunction "RESET_P$3") (pintype "bidirectional"))
    )
    (net (code "65") (name "SWD_RST_4") (class "Default")
      (node (ref "RN4") (pin "3") (pinfunction "1_3") (pintype "passive"))
      (node (ref "U4") (pin "P$3") (pinfunction "RESET_P$3") (pintype "bidirectional"))
    )
    (net (code "66") (name "SWD_RST_5") (class "Default")
      (node (ref "RN5") (pin "4") (pinfunction "1_4") (pintype "passive"))
      (node (ref "U5") (pin "P$3") (pinfunction "RESET_P$3") (pintype "bidirectional"))
    )
    (net (code "67") (name "VIN") (class "Default")
      (node (ref "C1") (pin "P$1") (pinfunction "P$1_P$1") (pintype "passive"))
      (node (ref "C2") (pin "P$1") (pinfunction "P$1_P$1") (pintype "passive"))
      (node (ref "C20") (pin "P$1") (pinfunction "P$1_P$1") (pintype "passive"))
      (node (ref "C3") (pin "P$1") (pinfunction "P$1_P$1") (pintype "passive"))
      (node (ref "C4") (pin "P$1") (pinfunction "P$1_P$1") (pintype "passive"))
      (node (ref "C5") (pin "P$1") (pinfunction "P$1_P$1") (pintype "passive"))
      (node (ref "D3") (pin "CATHODE") (pinfunction "CATHODE_CATHODE") (pintype "bidirectional"))
      (node (ref "U1") (pin "P$2") (pinfunction "VIN_P$2") (pintype "power_in"))
      (node (ref "U2") (pin "P$2") (pinfunction "VIN_P$2") (pintype "power_in"))
      (node (ref "U3") (pin "P$2") (pinfunction "VIN_P$2") (pintype "power_in"))
      (node (ref "U4") (pin "P$2") (pinfunction "VIN_P$2") (pintype "power_in"))
      (node (ref "U5") (pin "P$2") (pinfunction "VIN_P$2") (pintype "power_in"))
      (node (ref "U7") (pin "3") (pinfunction "IN_3") (pintype "input"))
    )
    (net (code "68") (name "unconnected-(J2-PIN1-PadP$2)") (class "Default")
      (node (ref "J2") (pin "P$2") (pinfunction "PIN1_P$2") (pintype "bidirectional"))
    )
    (net (code "69") (name "unconnected-(J2-PIN2-PadP$3)") (class "Default")
      (node (ref "J2") (pin "P$3") (pinfunction "PIN2_P$3") (pintype "bidirectional"))
    )
    (net (code "70") (name "unconnected-(RN5-Pad1)") (class "Default")
      (node (ref "RN5") (pin "1") (pinfunction "1_1") (pintype "passive"))
    )
    (net (code "71") (name "unconnected-(RN7D-1-Pad4)") (class "Default")
      (node (ref "RN7") (pin "4") (pinfunction "1_4") (pintype "passive"))
    )
    (net (code "72") (name "unconnected-(S2-O-Pad1)") (class "Default")
      (node (ref "S2") (pin "1") (pinfunction "O_1") (pintype "passive"))
    )
    (net (code "73") (name "unconnected-(U6B-P16-Pad19)") (class "Default")
      (node (ref "U6") (pin "19") (pinfunction "P16_19") (pintype "bidirectional"))
    )
  )
)
